# Operant-Front-Bonsai.net
KiCad netlist of a schematic drawn in EAGLE
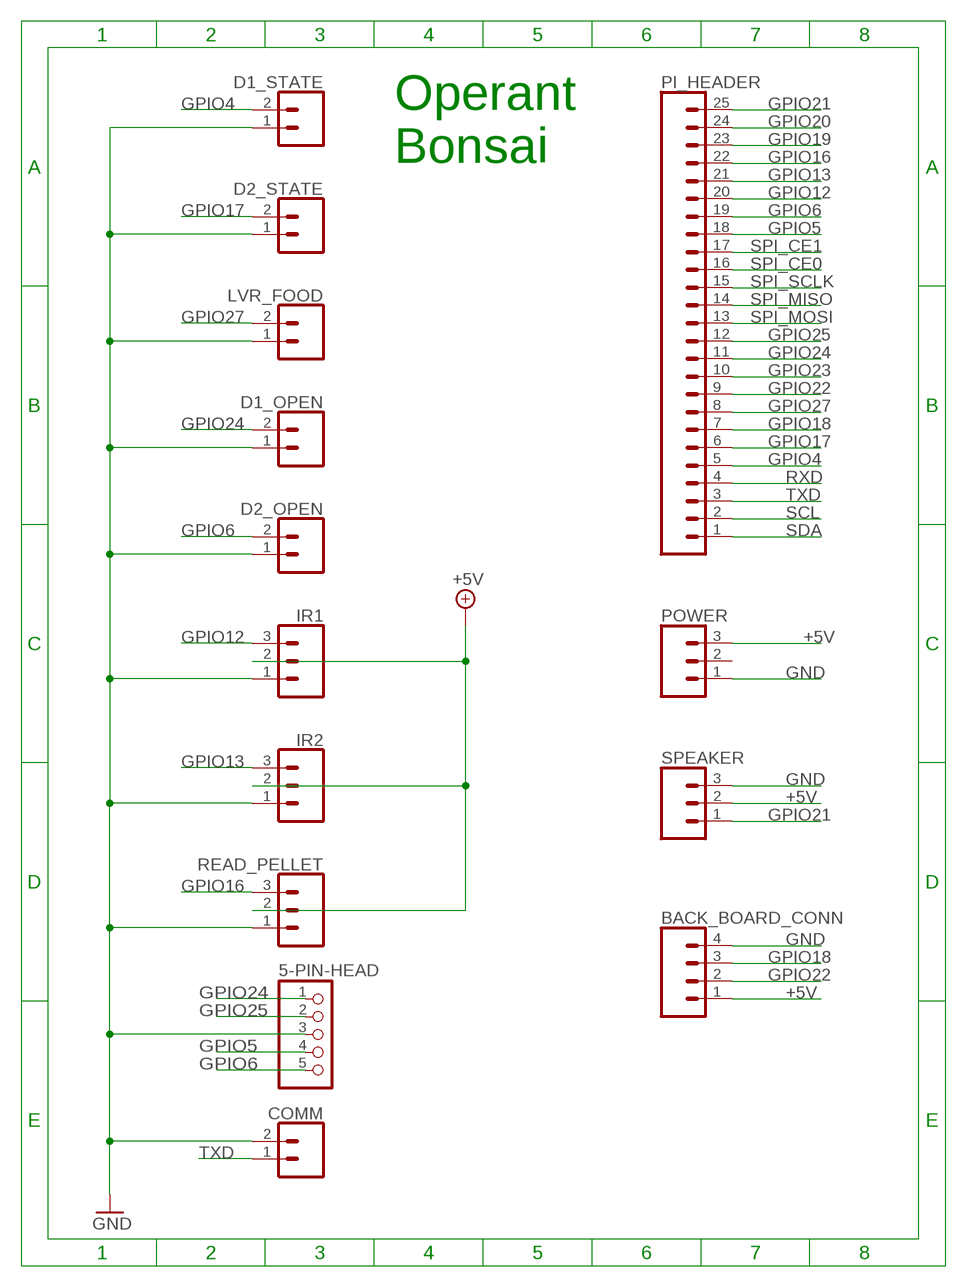
[diagram p0: schematic, sheet 1]

(export (version "E")
  (design (tool "Eeschema 10.0.6"))
  (components
    (comp (ref "5-PIN-HEAD")
      (value "PINHD-1X5")
      (footprint "eagle-import:1X05")
      (libsource (lib "eagle-import") (part "PINHD-1X5"))
    )
    (comp (ref "BACK_BOARD_CONN")
      (value "CONN_04JST-PTH")
      (footprint "eagle-import:JST-4-PTH")
      (libsource (lib "eagle-import") (part "CONN_04JST-PTH"))
    )
    (comp (ref "COMM")
      (value "CONN_02JST-PTH-2")
      (footprint "eagle-import:JST-2-PTH")
      (libsource (lib "eagle-import") (part "CONN_02JST-PTH-2"))
    )
    (comp (ref "D1_OPEN")
      (value "CONN_02JST-PTH-2")
      (footprint "eagle-import:JST-2-PTH")
      (libsource (lib "eagle-import") (part "CONN_02JST-PTH-2"))
    )
    (comp (ref "D1_STATE")
      (value "CONN_02JST-PTH-2")
      (footprint "eagle-import:JST-2-PTH")
      (libsource (lib "eagle-import") (part "CONN_02JST-PTH-2"))
    )
    (comp (ref "D2_OPEN")
      (value "CONN_02JST-PTH-2")
      (footprint "eagle-import:JST-2-PTH")
      (libsource (lib "eagle-import") (part "CONN_02JST-PTH-2"))
    )
    (comp (ref "D2_STATE")
      (value "CONN_02JST-PTH-2")
      (footprint "eagle-import:JST-2-PTH")
      (libsource (lib "eagle-import") (part "CONN_02JST-PTH-2"))
    )
    (comp (ref "IR1")
      (value "CONN_03JST-PTH")
      (footprint "eagle-import:JST-3-PTH")
      (libsource (lib "eagle-import") (part "CONN_03JST-PTH"))
    )
    (comp (ref "IR2")
      (value "CONN_03JST-PTH")
      (footprint "eagle-import:JST-3-PTH")
      (libsource (lib "eagle-import") (part "CONN_03JST-PTH"))
    )
    (comp (ref "LVR_FOOD")
      (value "CONN_02JST-PTH-2")
      (footprint "eagle-import:JST-2-PTH")
      (libsource (lib "eagle-import") (part "CONN_02JST-PTH-2"))
    )
    (comp (ref "PI_HEADER")
      (value "CONN_25")
      (footprint "eagle-import:1X25")
      (libsource (lib "eagle-import") (part "CONN_25"))
    )
    (comp (ref "POWER")
      (value "CONN_03")
      (footprint "eagle-import:1X03")
      (libsource (lib "eagle-import") (part "CONN_03"))
    )
    (comp (ref "READ_PELLET")
      (value "CONN_03JST-PTH")
      (footprint "eagle-import:JST-3-PTH")
      (libsource (lib "eagle-import") (part "CONN_03JST-PTH"))
    )
    (comp (ref "SPEAKER")
      (value "CONN_03JST-PTH")
      (footprint "eagle-import:JST-3-PTH")
      (libsource (lib "eagle-import") (part "CONN_03JST-PTH"))
    )
  )
  (nets
    (net (code "1") (name "+5V") (class "Default")
      (node (ref "BACK_BOARD_CONN") (pin "1") (pinfunction "1_1") (pintype "passive"))
      (node (ref "IR1") (pin "2") (pinfunction "2_2") (pintype "passive"))
      (node (ref "IR2") (pin "2") (pinfunction "2_2") (pintype "passive"))
      (node (ref "POWER") (pin "3") (pinfunction "3_3") (pintype "passive"))
      (node (ref "READ_PELLET") (pin "2") (pinfunction "2_2") (pintype "passive"))
      (node (ref "SPEAKER") (pin "2") (pinfunction "2_2") (pintype "passive"))
    )
    (net (code "2") (name "/GPIO4") (class "Default")
      (node (ref "D1_STATE") (pin "2") (pinfunction "2_2") (pintype "passive"))
      (node (ref "PI_HEADER") (pin "5") (pinfunction "5_5") (pintype "passive"))
    )
    (net (code "3") (name "/GPIO5") (class "Default")
      (node (ref "5-PIN-HEAD") (pin "4") (pinfunction "4_4") (pintype "passive"))
      (node (ref "PI_HEADER") (pin "18") (pinfunction "18_18") (pintype "passive"))
    )
    (net (code "4") (name "/GPIO6") (class "Default")
      (node (ref "5-PIN-HEAD") (pin "5") (pinfunction "5_5") (pintype "passive"))
      (node (ref "D2_OPEN") (pin "2") (pinfunction "2_2") (pintype "passive"))
      (node (ref "PI_HEADER") (pin "19") (pinfunction "19_19") (pintype "passive"))
    )
    (net (code "5") (name "/GPIO12") (class "Default")
      (node (ref "IR1") (pin "3") (pinfunction "3_3") (pintype "passive"))
      (node (ref "PI_HEADER") (pin "20") (pinfunction "20_20") (pintype "passive"))
    )
    (net (code "6") (name "/GPIO13") (class "Default")
      (node (ref "IR2") (pin "3") (pinfunction "3_3") (pintype "passive"))
      (node (ref "PI_HEADER") (pin "21") (pinfunction "21_21") (pintype "passive"))
    )
    (net (code "7") (name "/GPIO16") (class "Default")
      (node (ref "PI_HEADER") (pin "22") (pinfunction "22_22") (pintype "passive"))
      (node (ref "READ_PELLET") (pin "3") (pinfunction "3_3") (pintype "passive"))
    )
    (net (code "8") (name "/GPIO17") (class "Default")
      (node (ref "D2_STATE") (pin "2") (pinfunction "2_2") (pintype "passive"))
      (node (ref "PI_HEADER") (pin "6") (pinfunction "6_6") (pintype "passive"))
    )
    (net (code "9") (name "/GPIO18") (class "Default")
      (node (ref "BACK_BOARD_CONN") (pin "3") (pinfunction "3_3") (pintype "passive"))
      (node (ref "PI_HEADER") (pin "7") (pinfunction "7_7") (pintype "passive"))
    )
    (net (code "10") (name "/GPIO19") (class "Default")
      (node (ref "PI_HEADER") (pin "23") (pinfunction "23_23") (pintype "passive"))
    )
    (net (code "11") (name "/GPIO20") (class "Default")
      (node (ref "PI_HEADER") (pin "24") (pinfunction "24_24") (pintype "passive"))
    )
    (net (code "12") (name "/GPIO21") (class "Default")
      (node (ref "PI_HEADER") (pin "25") (pinfunction "25_25") (pintype "passive"))
      (node (ref "SPEAKER") (pin "1") (pinfunction "1_1") (pintype "passive"))
    )
    (net (code "13") (name "/GPIO22") (class "Default")
      (node (ref "BACK_BOARD_CONN") (pin "2") (pinfunction "2_2") (pintype "passive"))
      (node (ref "PI_HEADER") (pin "9") (pinfunction "9_9") (pintype "passive"))
    )
    (net (code "14") (name "/GPIO23") (class "Default")
      (node (ref "PI_HEADER") (pin "10") (pinfunction "10_10") (pintype "passive"))
    )
    (net (code "15") (name "/GPIO24") (class "Default")
      (node (ref "5-PIN-HEAD") (pin "1") (pinfunction "1_1") (pintype "passive"))
      (node (ref "D1_OPEN") (pin "2") (pinfunction "2_2") (pintype "passive"))
      (node (ref "PI_HEADER") (pin "11") (pinfunction "11_11") (pintype "passive"))
    )
    (net (code "16") (name "/GPIO25") (class "Default")
      (node (ref "5-PIN-HEAD") (pin "2") (pinfunction "2_2") (pintype "passive"))
      (node (ref "PI_HEADER") (pin "12") (pinfunction "12_12") (pintype "passive"))
    )
    (net (code "17") (name "/GPIO27") (class "Default")
      (node (ref "LVR_FOOD") (pin "2") (pinfunction "2_2") (pintype "passive"))
      (node (ref "PI_HEADER") (pin "8") (pinfunction "8_8") (pintype "passive"))
    )
    (net (code "18") (name "/RXD") (class "Default")
      (node (ref "PI_HEADER") (pin "4") (pinfunction "4_4") (pintype "passive"))
    )
    (net (code "19") (name "/SCL") (class "Default")
      (node (ref "PI_HEADER") (pin "2") (pinfunction "2_2") (pintype "passive"))
    )
    (net (code "20") (name "/SDA") (class "Default")
      (node (ref "PI_HEADER") (pin "1") (pinfunction "1_1") (pintype "passive"))
    )
    (net (code "21") (name "/SPI_CE0") (class "Default")
      (node (ref "PI_HEADER") (pin "16") (pinfunction "16_16") (pintype "passive"))
    )
    (net (code "22") (name "/SPI_CE1") (class "Default")
      (node (ref "PI_HEADER") (pin "17") (pinfunction "17_17") (pintype "passive"))
    )
    (net (code "23") (name "/SPI_MISO") (class "Default")
      (node (ref "PI_HEADER") (pin "14") (pinfunction "14_14") (pintype "passive"))
    )
    (net (code "24") (name "/SPI_MOSI") (class "Default")
      (node (ref "PI_HEADER") (pin "13") (pinfunction "13_13") (pintype "passive"))
    )
    (net (code "25") (name "/SPI_SCLK") (class "Default")
      (node (ref "PI_HEADER") (pin "15") (pinfunction "15_15") (pintype "passive"))
    )
    (net (code "26") (name "/TXD") (class "Default")
      (node (ref "COMM") (pin "1") (pinfunction "1_1") (pintype "passive"))
      (node (ref "PI_HEADER") (pin "3") (pinfunction "3_3") (pintype "passive"))
    )
    (net (code "27") (name "GND") (class "Default")
      (node (ref "5-PIN-HEAD") (pin "3") (pinfunction "3_3") (pintype "passive"))
      (node (ref "BACK_BOARD_CONN") (pin "4") (pinfunction "4_4") (pintype "passive"))
      (node (ref "COMM") (pin "2") (pinfunction "2_2") (pintype "passive"))
      (node (ref "D1_OPEN") (pin "1") (pinfunction "1_1") (pintype "passive"))
      (node (ref "D1_STATE") (pin "1") (pinfunction "1_1") (pintype "passive"))
      (node (ref "D2_OPEN") (pin "1") (pinfunction "1_1") (pintype "passive"))
      (node (ref "D2_STATE") (pin "1") (pinfunction "1_1") (pintype "passive"))
      (node (ref "IR1") (pin "1") (pinfunction "1_1") (pintype "passive"))
      (node (ref "IR2") (pin "1") (pinfunction "1_1") (pintype "passive"))
      (node (ref "LVR_FOOD") (pin "1") (pinfunction "1_1") (pintype "passive"))
      (node (ref "POWER") (pin "1") (pinfunction "1_1") (pintype "passive"))
      (node (ref "READ_PELLET") (pin "1") (pinfunction "1_1") (pintype "passive"))
      (node (ref "SPEAKER") (pin "3") (pinfunction "3_3") (pintype "passive"))
    )
    (net (code "28") (name "unconnected-(POWER-Pad2)") (class "Default")
      (node (ref "POWER") (pin "2") (pinfunction "2_2") (pintype "passive"))
    )
  )
)
